# Power_Supply.net
KiCad netlist of a schematic drawn in Altium Designer
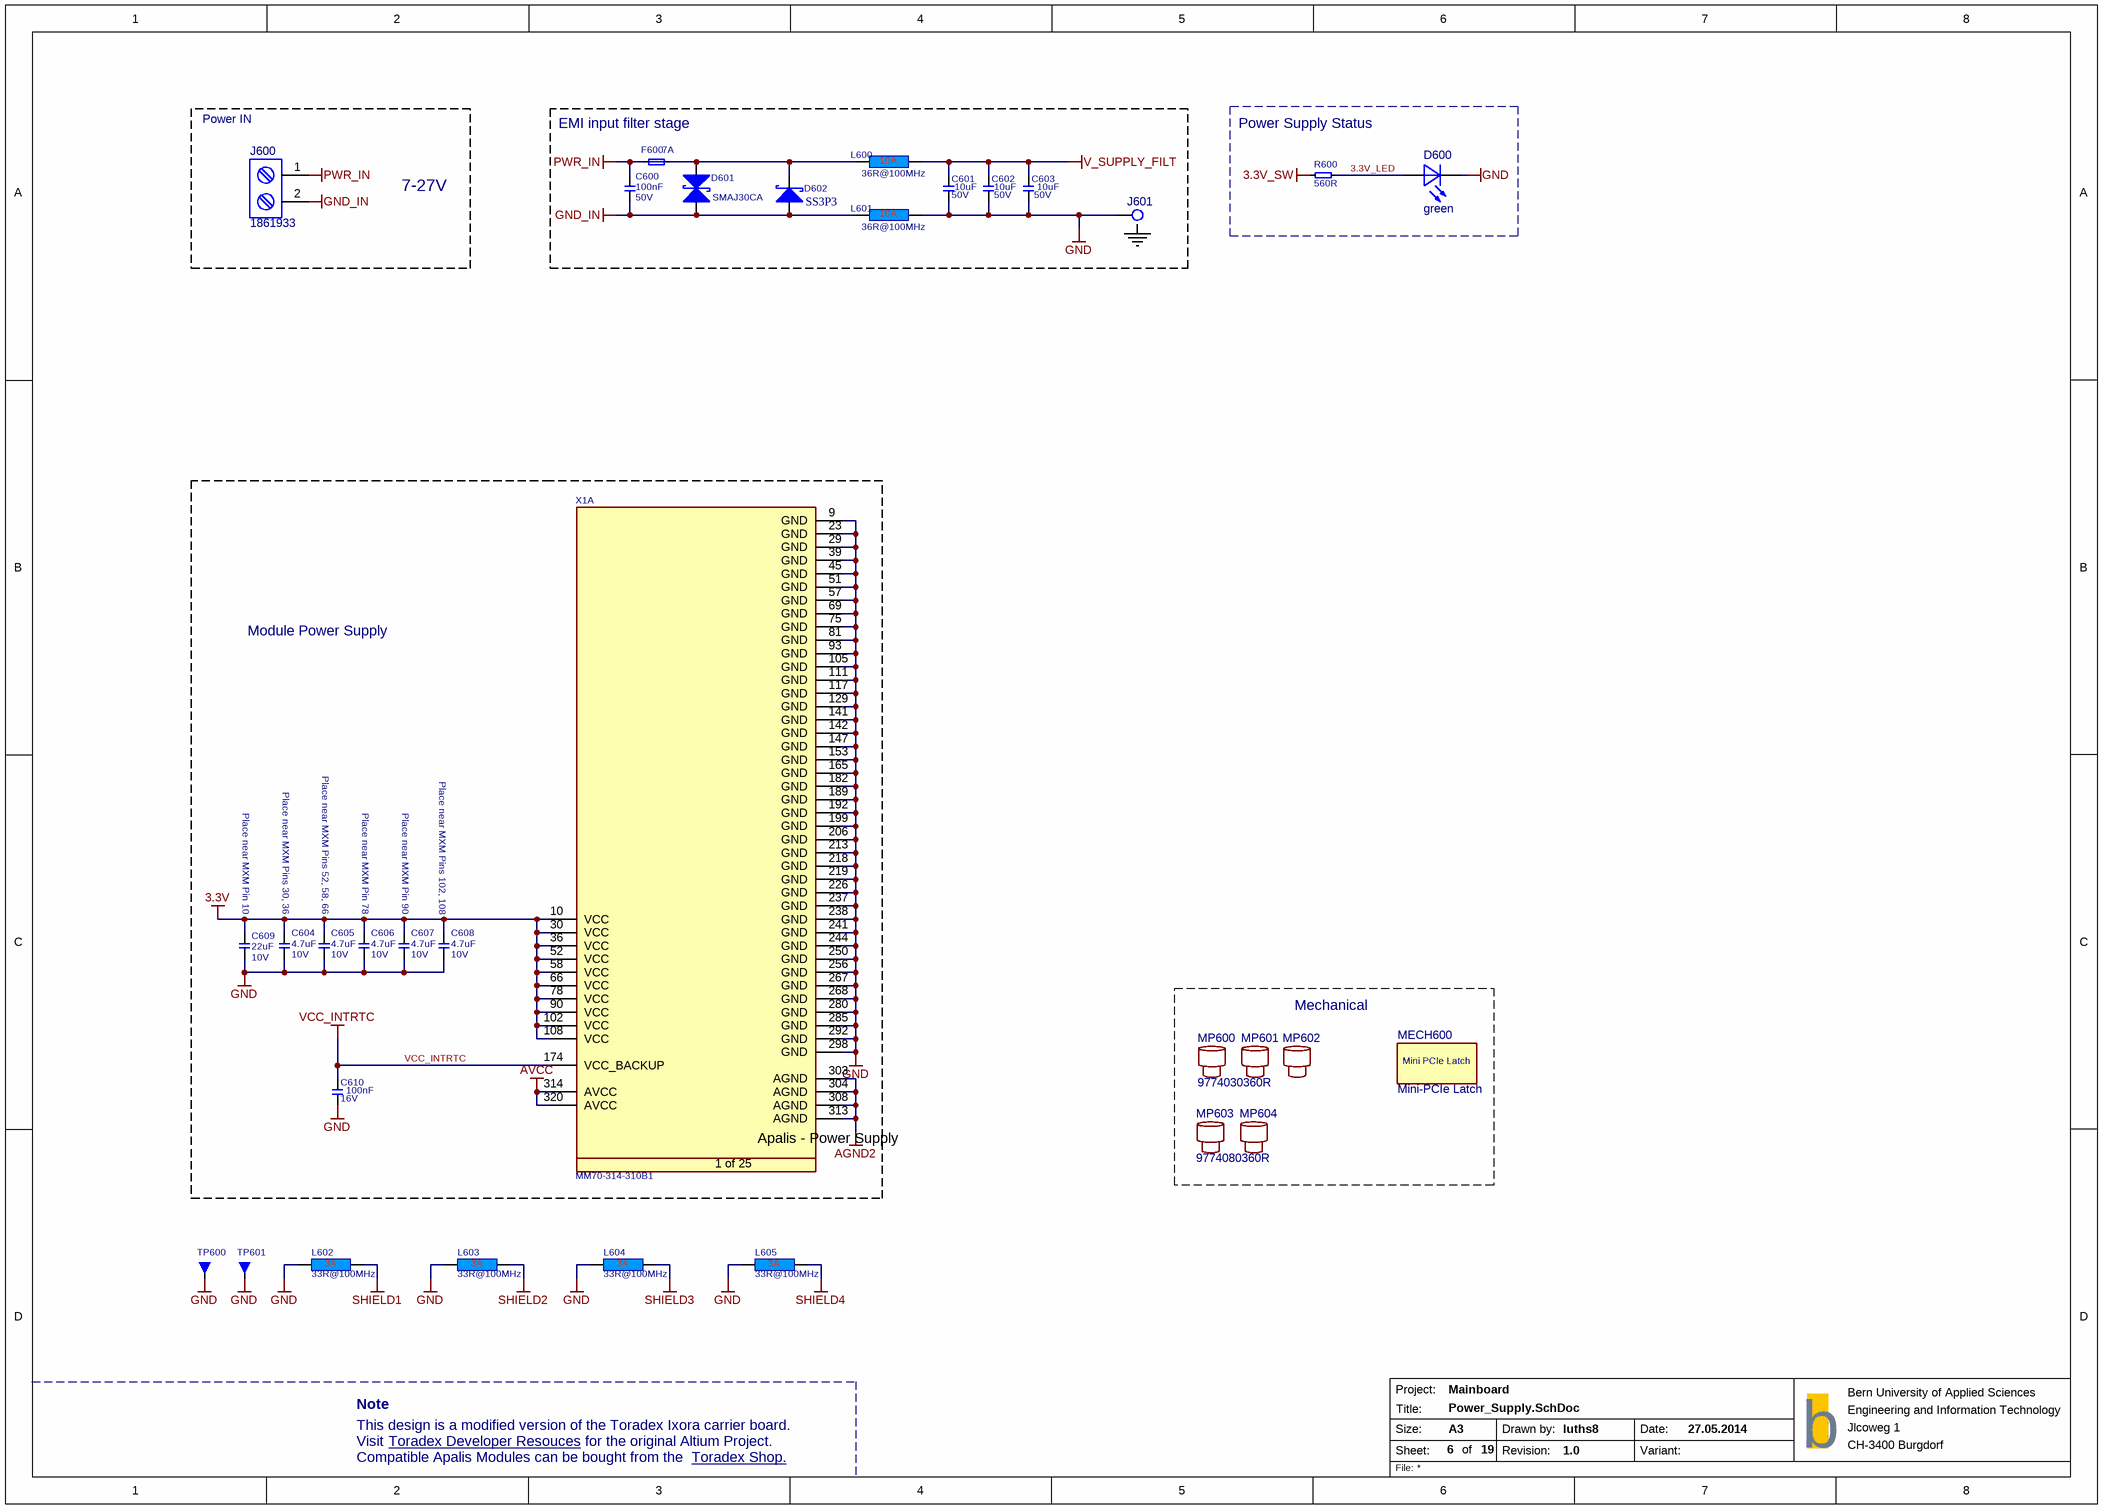
[diagram p0: Power_Supply.SchDoc]

(export (version "E")
  (design (tool "Eeschema 10.0.6"))
  (components
    (comp (ref "C600")
      (value "100nF")
      (footprint "SMD0603CAP")
      (description "Capacitor Ceramic X7R 100nF 50V 20% 0603")
      (fields (field (name "TOLERANCE") "20%") (field (name "RATING") "50V"))
      (libsource (lib "Ixora") (part "C-X7R-100nF-50V-20%-0603"))
    )
    (comp (ref "C601")
      (value "10uF")
      (footprint "SMD1210CAP")
      (description "Capacitor Ceramic X5R 10uF 50V 20% 1210")
      (fields (field (name "TOLERANCE") "20%") (field (name "RATING") "50V"))
      (libsource (lib "Ixora") (part "C-X5R-10uF-50V-20%-1210"))
    )
    (comp (ref "C602")
      (value "10uF")
      (footprint "SMD1210CAP")
      (description "Capacitor Ceramic X5R 10uF 50V 20% 1210")
      (fields (field (name "TOLERANCE") "20%") (field (name "RATING") "50V"))
      (libsource (lib "Ixora") (part "C-X5R-10uF-50V-20%-1210"))
    )
    (comp (ref "C603")
      (value "10uF")
      (footprint "SMD1210CAP")
      (description "Capacitor Ceramic X5R 10uF 50V 20% 1210")
      (fields (field (name "TOLERANCE") "20%") (field (name "RATING") "50V"))
      (libsource (lib "Ixora") (part "C-X5R-10uF-50V-20%-1210"))
    )
    (comp (ref "C604")
      (value "4.7uF")
      (footprint "SMD0603CAP")
      (description "Capacitor Ceramic X5R 4.7uF 10V 10% 0603")
      (fields (field (name "TOLERANCE") "10%") (field (name "RATING") "10V"))
      (libsource (lib "Ixora") (part "C-X5R-4.7uF-10V-10%-0603"))
    )
    (comp (ref "C605")
      (value "4.7uF")
      (footprint "SMD0603CAP")
      (description "Capacitor Ceramic X5R 4.7uF 10V 10% 0603")
      (fields (field (name "TOLERANCE") "10%") (field (name "RATING") "10V"))
      (libsource (lib "Ixora") (part "C-X5R-4.7uF-10V-10%-0603"))
    )
    (comp (ref "C606")
      (value "4.7uF")
      (footprint "SMD0603CAP")
      (description "Capacitor Ceramic X5R 4.7uF 10V 10% 0603")
      (fields (field (name "TOLERANCE") "10%") (field (name "RATING") "10V"))
      (libsource (lib "Ixora") (part "C-X5R-4.7uF-10V-10%-0603"))
    )
    (comp (ref "C607")
      (value "4.7uF")
      (footprint "SMD0603CAP")
      (description "Capacitor Ceramic X5R 4.7uF 10V 10% 0603")
      (fields (field (name "TOLERANCE") "10%") (field (name "RATING") "10V"))
      (libsource (lib "Ixora") (part "C-X5R-4.7uF-10V-10%-0603"))
    )
    (comp (ref "C608")
      (value "4.7uF")
      (footprint "SMD0603CAP")
      (description "Capacitor Ceramic X5R 4.7uF 10V 10% 0603")
      (fields (field (name "TOLERANCE") "10%") (field (name "RATING") "10V"))
      (libsource (lib "Ixora") (part "C-X5R-4.7uF-10V-10%-0603"))
    )
    (comp (ref "C609")
      (value "22uF")
      (footprint "SMD0805CAP")
      (description "Capacitor Ceramic X5R 22uF 10V 20% 0805")
      (fields (field (name "TOLERANCE") "20%") (field (name "RATING") "10V"))
      (libsource (lib "Ixora") (part "C-X5R-22uF-10V-20%-0805"))
    )
    (comp (ref "C610")
      (value "100nF")
      (footprint "SMD0603CAP")
      (description "Capacitor Ceramic X7R 100nF 16V 10% 0603")
      (fields (field (name "TOLERANCE") "10%") (field (name "RATING") "16V"))
      (libsource (lib "Ixora") (part "C-X7R-100nF-16V-10%-0402"))
    )
    (comp (ref "D600")
      (value "green")
      (footprint "LED")
      (description "LED green")
      (fields (field (name "MANUFACTURER PART NO.") "LGM67KG1J224Z"))
      (libsource (lib "Audio-Streamer") (part "LED green"))
    )
    (comp (ref "D601")
      (value "D-Littelfuse-SMAJ30CA-Schottky")
      (footprint "T_LITTLEFUSE_SMAJ30CA")
      (description "Bidirectional ESD protection")
      (fields (field (name "MANUFACTURER PART NO.") "SMAJ30CA"))
      (libsource (lib "Ixora") (part "D-Littelfuse-SMAJ30CA-Schottky"))
    )
    (comp (ref "D602")
      (value "SS3P3")
      (footprint "T_VISHAY_SS3P3")
      (description "SS3P3-E3/84A Schottky Diode")
      (fields (field (name "MANUFACTURER PART NO.") "SS3P3-E3/84A"))
      (libsource (lib "Ixora") (part "D-Vishay-SS3P3-E3/84A-Schottky"))
    )
    (comp (ref "F600")
      (value "7A")
      (footprint "T_Littelfuse_0458")
      (description "Fuse 7A Fast")
      (fields (field (name "MANUFACTURER PART NO.") "0458007"))
      (libsource (lib "Ixora") (part "F-Littelfuse-0458007"))
    )
    (comp (ref "J600")
      (value "1861933")
      (footprint "1861933")
      (description "Screw Terminal, 2 Position, 5mm Spacing")
      (libsource (lib "Audio-Streamer") (part "1861933"))
    )
    (comp (ref "J601")
      (value "Solder Pin")
      (footprint "SOLDER_PIN")
      (libsource (lib "Audio-Streamer") (part "Solder Pin"))
    )
    (comp (ref "L600")
      (value "36R@100MHz")
      (footprint "T_Laird_35F0121-0SR-10")
      (description "Power Supply FB 10A")
      (fields (field (name "TOLERANCE") "25%"))
      (libsource (lib "Ixora") (part "L-Laird-35F0121-0SR-10-10A-25%"))
    )
    (comp (ref "L601")
      (value "36R@100MHz")
      (footprint "T_Laird_35F0121-0SR-10")
      (description "Power Supply FB 10A")
      (fields (field (name "TOLERANCE") "25%"))
      (libsource (lib "Ixora") (part "L-Laird-35F0121-0SR-10-10A-25%"))
    )
    (comp (ref "L602")
      (value "33R@100MHz")
      (footprint "INDC1608X95N")
      (description "33R@100MHz 3A EMI FILTER")
      (fields (field (name "TOLERANCE") "25%"))
      (libsource (lib "Ixora") (part "L-33R@100MHz-3A-25%-0603"))
    )
    (comp (ref "L603")
      (value "33R@100MHz")
      (footprint "INDC1608X95N")
      (description "33R@100MHz 3A EMI FILTER")
      (fields (field (name "TOLERANCE") "25%"))
      (libsource (lib "Ixora") (part "L-33R@100MHz-3A-25%-0603"))
    )
    (comp (ref "L604")
      (value "33R@100MHz")
      (footprint "INDC1608X95N")
      (description "33R@100MHz 3A EMI FILTER")
      (fields (field (name "TOLERANCE") "25%"))
      (libsource (lib "Ixora") (part "L-33R@100MHz-3A-25%-0603"))
    )
    (comp (ref "L605")
      (value "33R@100MHz")
      (footprint "INDC1608X95N")
      (description "33R@100MHz 3A EMI FILTER")
      (fields (field (name "TOLERANCE") "25%"))
      (libsource (lib "Ixora") (part "L-33R@100MHz-3A-25%-0603"))
    )
    (comp (ref "MECH600")
      (value "Mini-PCIe Latch")
      (footprint "T_Molex_48099-5701")
      (fields (field (name "MANUFACTURER PART NO.") "48099-5701"))
      (libsource (lib "Ixora") (part "MECH-Molex-48099-5701"))
    )
    (comp (ref "MP600")
      (value "9774030360R")
      (description "Spacer M3 SMD")
      (libsource (lib "Audio-Streamer") (part "Spacer M3 SMD"))
    )
    (comp (ref "MP601")
      (value "9774030360R")
      (description "Spacer M3 SMD")
      (libsource (lib "Audio-Streamer") (part "Spacer M3 SMD"))
    )
    (comp (ref "MP602")
      (value "9774030360R")
      (description "Spacer M3 SMD")
      (libsource (lib "Audio-Streamer") (part "Spacer M3 SMD"))
    )
    (comp (ref "MP603")
      (value "9774080360R")
      (description "Spacer M3 SMD")
      (libsource (lib "Audio-Streamer") (part "Spacer M3 SMD"))
    )
    (comp (ref "MP604")
      (value "9774080360R")
      (description "Spacer M3 SMD")
      (libsource (lib "Audio-Streamer") (part "Spacer M3 SMD"))
    )
    (comp (ref "R600")
      (value "560R")
      (footprint "SMD0603RES")
      (description "Resistor 560 ohm 63mW 5% 0603")
      (fields (field (name "TOLERANCE") "5%"))
      (libsource (lib "Ixora") (part "R-560R-63mW-5%-0402"))
    )
    (comp (ref "TP600")
      (value "5011")
      (footprint "T_TP-THT - EYE")
      (description "Testpin Eye TH")
      (libsource (lib "Ixora") (part "TP-Keystone-5011"))
    )
    (comp (ref "TP601")
      (value "5011")
      (footprint "T_TP-THT - EYE")
      (description "Testpin Eye TH")
      (libsource (lib "Ixora") (part "TP-Keystone-5011"))
    )
    (comp (ref "X1")
      (value "CON-JAE-MM70-314-310B1-314-0.5mm")
      (footprint "T_JAE_MM70-314-310B1")
      (description "MXM3 Connector")
      (fields (field (name "MANUFACTURER PART NO.") "MM70-314-310B1"))
      (libsource (lib "Ixora") (part "CON-JAE-MM70-314-310B1-314-0.5mm"))
    )
  )
  (nets
    (net (code "1") (name "/3.3V_LED") (class "Default")
      (node (ref "D600") (pin "A") (pinfunction "A_A") (pintype "passive"))
      (node (ref "R600") (pin "2") (pinfunction "2_2") (pintype "passive"))
    )
    (net (code "2") (name "3.3V") (class "Default")
      (node (ref "C604") (pin "1") (pinfunction "1_1") (pintype "passive"))
      (node (ref "C605") (pin "1") (pinfunction "1_1") (pintype "passive"))
      (node (ref "C606") (pin "1") (pinfunction "1_1") (pintype "passive"))
      (node (ref "C607") (pin "1") (pinfunction "1_1") (pintype "passive"))
      (node (ref "C608") (pin "1") (pinfunction "1_1") (pintype "passive"))
      (node (ref "C609") (pin "1") (pinfunction "1_1") (pintype "passive"))
      (node (ref "X1") (pin "10") (pinfunction "VCC_10") (pintype "passive"))
      (node (ref "X1") (pin "102") (pinfunction "VCC_102") (pintype "passive"))
      (node (ref "X1") (pin "108") (pinfunction "VCC_108") (pintype "passive"))
      (node (ref "X1") (pin "30") (pinfunction "VCC_30") (pintype "passive"))
      (node (ref "X1") (pin "36") (pinfunction "VCC_36") (pintype "passive"))
      (node (ref "X1") (pin "52") (pinfunction "VCC_52") (pintype "passive"))
      (node (ref "X1") (pin "58") (pinfunction "VCC_58") (pintype "passive"))
      (node (ref "X1") (pin "66") (pinfunction "VCC_66") (pintype "passive"))
      (node (ref "X1") (pin "78") (pinfunction "VCC_78") (pintype "passive"))
      (node (ref "X1") (pin "90") (pinfunction "VCC_90") (pintype "passive"))
    )
    (net (code "3") (name "3.3V_SW") (class "Default")
      (node (ref "R600") (pin "1") (pinfunction "1_1") (pintype "passive"))
    )
    (net (code "4") (name "AGND2") (class "Default")
      (node (ref "X1") (pin "303") (pinfunction "AGND_303") (pintype "power_in"))
      (node (ref "X1") (pin "304") (pinfunction "AGND_304") (pintype "power_in"))
      (node (ref "X1") (pin "308") (pinfunction "AGND_308") (pintype "power_in"))
      (node (ref "X1") (pin "313") (pinfunction "AGND_313") (pintype "passive"))
    )
    (net (code "5") (name "AVCC") (class "Default")
      (node (ref "X1") (pin "314") (pinfunction "AVCC_314") (pintype "power_in"))
      (node (ref "X1") (pin "320") (pinfunction "AVCC_320") (pintype "passive"))
    )
    (net (code "6") (name "GND") (class "Default")
      (node (ref "C601") (pin "1") (pinfunction "1_1") (pintype "passive"))
      (node (ref "C602") (pin "1") (pinfunction "1_1") (pintype "passive"))
      (node (ref "C603") (pin "1") (pinfunction "1_1") (pintype "passive"))
      (node (ref "C604") (pin "2") (pinfunction "2_2") (pintype "passive"))
      (node (ref "C605") (pin "2") (pinfunction "2_2") (pintype "passive"))
      (node (ref "C606") (pin "2") (pinfunction "2_2") (pintype "passive"))
      (node (ref "C607") (pin "2") (pinfunction "2_2") (pintype "passive"))
      (node (ref "C608") (pin "2") (pinfunction "2_2") (pintype "passive"))
      (node (ref "C609") (pin "2") (pinfunction "2_2") (pintype "passive"))
      (node (ref "C610") (pin "1") (pinfunction "1_1") (pintype "passive"))
      (node (ref "D600") (pin "C") (pinfunction "C_C") (pintype "passive"))
      (node (ref "J601") (pin "1") (pinfunction "1_1") (pintype "passive"))
      (node (ref "L601") (pin "2") (pinfunction "2_2") (pintype "passive"))
      (node (ref "L602") (pin "1") (pinfunction "1_1") (pintype "passive"))
      (node (ref "L603") (pin "1") (pinfunction "1_1") (pintype "passive"))
      (node (ref "L604") (pin "1") (pinfunction "1_1") (pintype "passive"))
      (node (ref "L605") (pin "1") (pinfunction "1_1") (pintype "passive"))
      (node (ref "TP600") (pin "1") (pinfunction "1_1") (pintype "passive"))
      (node (ref "TP601") (pin "1") (pinfunction "1_1") (pintype "passive"))
      (node (ref "X1") (pin "105") (pinfunction "GND_105") (pintype "power_in"))
      (node (ref "X1") (pin "111") (pinfunction "GND_111") (pintype "power_in"))
      (node (ref "X1") (pin "117") (pinfunction "GND_117") (pintype "power_in"))
      (node (ref "X1") (pin "129") (pinfunction "GND_129") (pintype "power_in"))
      (node (ref "X1") (pin "141") (pinfunction "GND_141") (pintype "power_in"))
      (node (ref "X1") (pin "142") (pinfunction "GND_142") (pintype "power_in"))
      (node (ref "X1") (pin "147") (pinfunction "GND_147") (pintype "power_in"))
      (node (ref "X1") (pin "153") (pinfunction "GND_153") (pintype "power_in"))
      (node (ref "X1") (pin "165") (pinfunction "GND_165") (pintype "power_in"))
      (node (ref "X1") (pin "182") (pinfunction "GND_182") (pintype "power_in"))
      (node (ref "X1") (pin "189") (pinfunction "GND_189") (pintype "power_in"))
      (node (ref "X1") (pin "192") (pinfunction "GND_192") (pintype "power_in"))
      (node (ref "X1") (pin "199") (pinfunction "GND_199") (pintype "power_in"))
      (node (ref "X1") (pin "206") (pinfunction "GND_206") (pintype "power_in"))
      (node (ref "X1") (pin "213") (pinfunction "GND_213") (pintype "power_in"))
      (node (ref "X1") (pin "218") (pinfunction "GND_218") (pintype "power_in"))
      (node (ref "X1") (pin "219") (pinfunction "GND_219") (pintype "power_in"))
      (node (ref "X1") (pin "226") (pinfunction "GND_226") (pintype "power_in"))
      (node (ref "X1") (pin "23") (pinfunction "GND_23") (pintype "passive"))
      (node (ref "X1") (pin "237") (pinfunction "GND_237") (pintype "power_in"))
      (node (ref "X1") (pin "238") (pinfunction "GND_238") (pintype "power_in"))
      (node (ref "X1") (pin "241") (pinfunction "GND_241") (pintype "power_in"))
      (node (ref "X1") (pin "244") (pinfunction "GND_244") (pintype "power_in"))
      (node (ref "X1") (pin "250") (pinfunction "GND_250") (pintype "power_in"))
      (node (ref "X1") (pin "256") (pinfunction "GND_256") (pintype "power_in"))
      (node (ref "X1") (pin "267") (pinfunction "GND_267") (pintype "power_in"))
      (node (ref "X1") (pin "268") (pinfunction "GND_268") (pintype "power_in"))
      (node (ref "X1") (pin "280") (pinfunction "GND_280") (pintype "power_in"))
      (node (ref "X1") (pin "285") (pinfunction "GND_285") (pintype "power_in"))
      (node (ref "X1") (pin "29") (pinfunction "GND_29") (pintype "power_in"))
      (node (ref "X1") (pin "292") (pinfunction "GND_292") (pintype "power_in"))
      (node (ref "X1") (pin "298") (pinfunction "GND_298") (pintype "power_in"))
      (node (ref "X1") (pin "39") (pinfunction "GND_39") (pintype "power_in"))
      (node (ref "X1") (pin "45") (pinfunction "GND_45") (pintype "power_in"))
      (node (ref "X1") (pin "51") (pinfunction "GND_51") (pintype "power_in"))
      (node (ref "X1") (pin "57") (pinfunction "GND_57") (pintype "power_in"))
      (node (ref "X1") (pin "69") (pinfunction "GND_69") (pintype "power_in"))
      (node (ref "X1") (pin "75") (pinfunction "GND_75") (pintype "power_in"))
      (node (ref "X1") (pin "81") (pinfunction "GND_81") (pintype "power_in"))
      (node (ref "X1") (pin "9") (pinfunction "GND_9") (pintype "passive"))
      (node (ref "X1") (pin "93") (pinfunction "GND_93") (pintype "power_in"))
    )
    (net (code "7") (name "GND_IN") (class "Default")
      (node (ref "C600") (pin "1") (pinfunction "1_1") (pintype "passive"))
      (node (ref "D601") (pin "2") (pinfunction "Anode_2") (pintype "passive"))
      (node (ref "D602") (pin "2") (pinfunction "2_2") (pintype "passive"))
      (node (ref "J600") (pin "2") (pinfunction "2_2") (pintype "passive"))
      (node (ref "L601") (pin "1") (pinfunction "1_1") (pintype "passive"))
    )
    (net (code "8") (name "Net-(D601-Cathode)") (class "Default")
      (node (ref "D601") (pin "1") (pinfunction "Cathode_1") (pintype "passive"))
      (node (ref "D602") (pin "1") (pinfunction "1_1") (pintype "passive"))
      (node (ref "F600") (pin "2") (pinfunction "2_2") (pintype "passive"))
      (node (ref "L600") (pin "1") (pinfunction "1_1") (pintype "passive"))
    )
    (net (code "9") (name "PWR_IN") (class "Default")
      (node (ref "C600") (pin "2") (pinfunction "2_2") (pintype "passive"))
      (node (ref "F600") (pin "1") (pinfunction "1_1") (pintype "passive"))
      (node (ref "J600") (pin "1") (pinfunction "1_1") (pintype "passive"))
    )
    (net (code "10") (name "SHIELD1") (class "Default")
      (node (ref "L602") (pin "2") (pinfunction "2_2") (pintype "passive"))
    )
    (net (code "11") (name "SHIELD2") (class "Default")
      (node (ref "L603") (pin "2") (pinfunction "2_2") (pintype "passive"))
    )
    (net (code "12") (name "SHIELD3") (class "Default")
      (node (ref "L604") (pin "2") (pinfunction "2_2") (pintype "passive"))
    )
    (net (code "13") (name "SHIELD4") (class "Default")
      (node (ref "L605") (pin "2") (pinfunction "2_2") (pintype "passive"))
    )
    (net (code "14") (name "VCC_INTRTC") (class "Default")
      (node (ref "C610") (pin "2") (pinfunction "2_2") (pintype "passive"))
      (node (ref "X1") (pin "174") (pinfunction "VCC_BACKUP_174") (pintype "passive"))
    )
    (net (code "15") (name "V_SUPPLY_FILT") (class "Default")
      (node (ref "C601") (pin "2") (pinfunction "2_2") (pintype "passive"))
      (node (ref "C602") (pin "2") (pinfunction "2_2") (pintype "passive"))
      (node (ref "C603") (pin "2") (pinfunction "2_2") (pintype "passive"))
      (node (ref "L600") (pin "2") (pinfunction "2_2") (pintype "passive"))
    )
  )
)
